# completed.net
KiCad netlist of a schematic drawn in Altium Designer
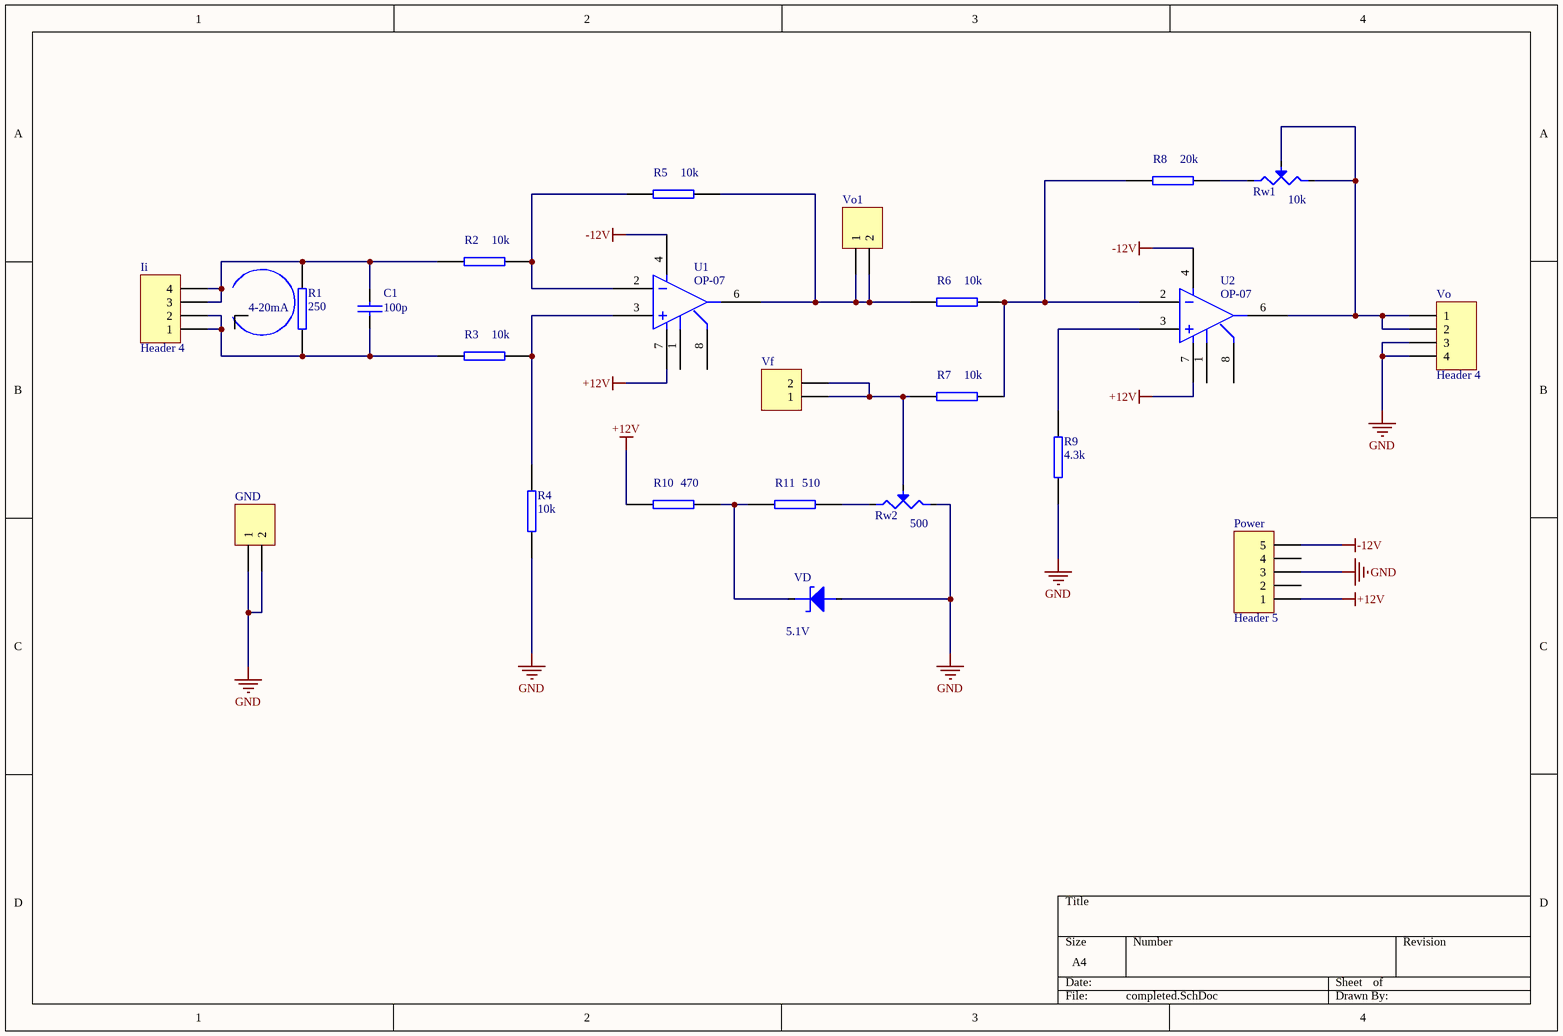
[diagram p0: completed.SchDoc]

(export (version "E")
  (design (tool "Eeschema 10.0.6"))
  (components
    (comp (ref "C1")
      (value "CAP")
      (footprint "RAD-0.2")
      (fields (field (name "ALTIUM_UNNAMED_1") "100p"))
      (libsource (lib "Schematic Linear") (part "CAP"))
    )
    (comp (ref "GND")
      (value "Header 2")
      (footprint "SIP-2")
      (description "Header, 2-Pin")
      (fields (field (name "PUBLISHER") "Altium Limited"))
      (libsource (lib "") (part "Header 2_1"))
    )
    (comp (ref "Ii")
      (value "Header 4")
      (footprint "SIP-4")
      (description "Header, 4-Pin")
      (fields (field (name "PUBLISHER") "Altium Limited"))
      (libsource (lib "Miscellaneous Connectors") (part "Header 4"))
    )
    (comp (ref "Power")
      (value "Header 5")
      (footprint "POWER PLUG5")
      (description "Header, 5-Pin")
      (fields (field (name "PUBLISHER") "Altium Limited"))
      (libsource (lib "Miscellaneous Connectors") (part "Header 5"))
    )
    (comp (ref "R1")
      (value "RES2")
      (footprint "AXIAL0.4")
      (fields (field (name "R1") "250"))
      (libsource (lib "Miscellaneous Devices") (part "RES2"))
    )
    (comp (ref "R2")
      (value "RES2")
      (footprint "AXIAL0.4")
      (fields (field (name "ALTIUM_UNNAMED_1") "10k"))
      (libsource (lib "Miscellaneous Devices") (part "RES2"))
    )
    (comp (ref "R3")
      (value "10k")
      (footprint "AXIAL0.4")
      (fields (field (name "Comment") "RES2"))
      (libsource (lib "Miscellaneous Devices") (part "RES2"))
    )
    (comp (ref "R4")
      (value "RES2")
      (footprint "AXIAL0.4")
      (fields (field (name "R1") "10k"))
      (libsource (lib "Miscellaneous Devices") (part "RES2"))
    )
    (comp (ref "R5")
      (value "RES2")
      (footprint "AXIAL0.4")
      (fields (field (name "ALTIUM_UNNAMED_1") "10k"))
      (libsource (lib "Miscellaneous Devices") (part "RES2"))
    )
    (comp (ref "R6")
      (value "10k")
      (footprint "AXIAL0.4")
      (fields (field (name "Comment") "RES2"))
      (libsource (lib "Miscellaneous Devices") (part "RES2"))
    )
    (comp (ref "R7")
      (value "RES2")
      (footprint "AXIAL0.4")
      (fields (field (name "ALTIUM_UNNAMED_1") "10k"))
      (libsource (lib "Miscellaneous Devices") (part "RES2"))
    )
    (comp (ref "R8")
      (value "20k")
      (footprint "AXIAL0.4")
      (fields (field (name "Comment") "RES2"))
      (libsource (lib "Miscellaneous Devices") (part "RES2"))
    )
    (comp (ref "R9")
      (value "4.3k")
      (footprint "AXIAL0.4")
      (fields (field (name "Comment") "RES2"))
      (libsource (lib "Miscellaneous Devices") (part "RES2"))
    )
    (comp (ref "R10")
      (value "RES2")
      (footprint "AXIAL0.4")
      (fields (field (name "VALUE'") "470"))
      (libsource (lib "Miscellaneous Devices") (part "RES2"))
    )
    (comp (ref "R11")
      (value "510")
      (footprint "AXIAL0.4")
      (fields (field (name "Comment") "RES2"))
      (libsource (lib "Miscellaneous Devices") (part "RES2"))
    )
    (comp (ref "Rw1")
      (value "10k")
      (footprint "VR-5")
      (description "Potentiometer")
      (fields (field (name "Comment") "POT1"))
      (libsource (lib "") (part "POT1_1"))
    )
    (comp (ref "Rw2")
      (value "500")
      (footprint "VR-5")
      (description "Potentiometer")
      (fields (field (name "Comment") "POT1"))
      (libsource (lib "Miscellaneous Devices") (part "POT1"))
    )
    (comp (ref "U1")
      (value "OP-07")
      (footprint "DIP-8")
      (libsource (lib "Schematic Operational Amplifiers") (part "OP-07"))
    )
    (comp (ref "U2")
      (value "OP-07")
      (footprint "DIP-8")
      (libsource (lib "Schematic Operational Amplifiers") (part "OP-07"))
    )
    (comp (ref "VD")
      (value "5.1V")
      (footprint "DIODE-0.4")
      (description "Zener Diode")
      (fields (field (name "Comment") "ZENER2"))
      (libsource (lib "Miscellaneous Devices") (part "ZENER2"))
    )
    (comp (ref "Vf")
      (value "Header 2")
      (footprint "SIP-2")
      (description "Header, 2-Pin")
      (fields (field (name "PUBLISHER") "Altium Limited"))
      (libsource (lib "Miscellaneous Connectors") (part "Header 2"))
    )
    (comp (ref "Vo")
      (value "Header 4")
      (footprint "SIP-4")
      (description "Header, 4-Pin")
      (fields (field (name "PUBLISHER") "Altium Limited"))
      (libsource (lib "") (part "Header 4_1"))
    )
    (comp (ref "Vo1")
      (value "Header 2")
      (footprint "SIP-2")
      (description "Header, 2-Pin")
      (fields (field (name "PUBLISHER") "Altium Limited"))
      (libsource (lib "") (part "Header 2_1"))
    )
  )
  (nets
    (net (code "1") (name "+12V") (class "Default")
      (node (ref "Power") (pin "1") (pinfunction "1_1") (pintype "passive"))
      (node (ref "R10") (pin "1") (pinfunction "1_1") (pintype "passive"))
      (node (ref "U1") (pin "7") (pintype "passive"))
      (node (ref "U2") (pin "7") (pintype "passive"))
    )
    (net (code "2") (name "-12V") (class "Default")
      (node (ref "Power") (pin "5") (pinfunction "5_5") (pintype "passive"))
      (node (ref "U1") (pin "4") (pintype "passive"))
      (node (ref "U2") (pin "4") (pintype "passive"))
    )
    (net (code "3") (name "GND") (class "Default")
      (node (ref "GND") (pin "1") (pinfunction "1_1") (pintype "passive"))
      (node (ref "GND") (pin "2") (pinfunction "2_2") (pintype "passive"))
      (node (ref "Power") (pin "3") (pinfunction "3_3") (pintype "passive"))
      (node (ref "R4") (pin "1") (pinfunction "1_1") (pintype "passive"))
      (node (ref "R9") (pin "1") (pinfunction "1_1") (pintype "passive"))
      (node (ref "Rw2") (pin "1") (pinfunction "2_1") (pintype "passive"))
      (node (ref "VD") (pin "1") (pinfunction "A_1") (pintype "passive"))
      (node (ref "Vo") (pin "3") (pinfunction "3_3") (pintype "passive"))
      (node (ref "Vo") (pin "4") (pinfunction "4_4") (pintype "passive"))
    )
    (net (code "4") (name "Net-(C1-Pad1)") (class "Default")
      (node (ref "C1") (pin "1") (pintype "passive"))
      (node (ref "Ii") (pin "3") (pinfunction "3_3") (pintype "passive"))
      (node (ref "Ii") (pin "4") (pinfunction "4_4") (pintype "passive"))
      (node (ref "R1") (pin "2") (pinfunction "2_2") (pintype "passive"))
      (node (ref "R2") (pin "1") (pinfunction "1_1") (pintype "passive"))
    )
    (net (code "5") (name "Net-(C1-Pad2)") (class "Default")
      (node (ref "C1") (pin "2") (pintype "passive"))
      (node (ref "Ii") (pin "1") (pinfunction "1_1") (pintype "passive"))
      (node (ref "Ii") (pin "2") (pinfunction "2_2") (pintype "passive"))
      (node (ref "R1") (pin "1") (pinfunction "1_1") (pintype "passive"))
      (node (ref "R3") (pin "1") (pinfunction "1_1") (pintype "passive"))
    )
    (net (code "6") (name "Net-(R2-Pad2)") (class "Default")
      (node (ref "R2") (pin "2") (pinfunction "2_2") (pintype "passive"))
      (node (ref "R5") (pin "1") (pinfunction "1_1") (pintype "passive"))
      (node (ref "U1") (pin "2") (pintype "passive"))
    )
    (net (code "7") (name "Net-(R3-Pad2)") (class "Default")
      (node (ref "R3") (pin "2") (pinfunction "2_2") (pintype "passive"))
      (node (ref "R4") (pin "2") (pinfunction "2_2") (pintype "passive"))
      (node (ref "U1") (pin "3") (pintype "passive"))
    )
    (net (code "8") (name "Net-(R5-Pad2)") (class "Default")
      (node (ref "R5") (pin "2") (pinfunction "2_2") (pintype "passive"))
      (node (ref "R6") (pin "1") (pinfunction "1_1") (pintype "passive"))
      (node (ref "U1") (pin "6") (pintype "passive"))
      (node (ref "Vo1") (pin "1") (pinfunction "1_1") (pintype "passive"))
      (node (ref "Vo1") (pin "2") (pinfunction "2_2") (pintype "passive"))
    )
    (net (code "9") (name "Net-(R6-Pad2)") (class "Default")
      (node (ref "R6") (pin "2") (pinfunction "2_2") (pintype "passive"))
      (node (ref "R7") (pin "2") (pinfunction "2_2") (pintype "passive"))
      (node (ref "R8") (pin "1") (pinfunction "1_1") (pintype "passive"))
      (node (ref "U2") (pin "2") (pintype "passive"))
    )
    (net (code "10") (name "Net-(R8-Pad2)") (class "Default")
      (node (ref "R8") (pin "2") (pinfunction "2_2") (pintype "passive"))
      (node (ref "Rw1") (pin "1") (pinfunction "1_1") (pintype "passive"))
    )
    (net (code "11") (name "Net-(R9-Pad2)") (class "Default")
      (node (ref "R9") (pin "2") (pinfunction "2_2") (pintype "passive"))
      (node (ref "U2") (pin "3") (pintype "passive"))
    )
    (net (code "12") (name "Net-(Rw1-W)") (class "Default")
      (node (ref "Rw1") (pin "2") (pinfunction "2_2") (pintype "passive"))
      (node (ref "Rw1") (pin "3") (pinfunction "W_3") (pintype "passive"))
      (node (ref "U2") (pin "6") (pintype "passive"))
      (node (ref "Vo") (pin "1") (pinfunction "1_1") (pintype "passive"))
      (node (ref "Vo") (pin "2") (pinfunction "2_2") (pintype "passive"))
    )
    (net (code "13") (name "Net-(Rw2-1)") (class "Default")
      (node (ref "R11") (pin "2") (pinfunction "2_2") (pintype "passive"))
      (node (ref "Rw2") (pin "2") (pinfunction "1_2") (pintype "passive"))
    )
    (net (code "14") (name "Net-(Rw2-W)") (class "Default")
      (node (ref "R7") (pin "1") (pinfunction "1_1") (pintype "passive"))
      (node (ref "Rw2") (pin "3") (pinfunction "W_3") (pintype "passive"))
      (node (ref "Vf") (pin "1") (pinfunction "1_1") (pintype "passive"))
      (node (ref "Vf") (pin "2") (pinfunction "2_2") (pintype "passive"))
    )
    (net (code "15") (name "Net-(VD-K)") (class "Default")
      (node (ref "R10") (pin "2") (pinfunction "2_2") (pintype "passive"))
      (node (ref "R11") (pin "1") (pinfunction "1_1") (pintype "passive"))
      (node (ref "VD") (pin "2") (pinfunction "K_2") (pintype "passive"))
    )
    (net (code "16") (name "unconnected-(Power-Pad2)") (class "Default")
      (node (ref "Power") (pin "2") (pinfunction "2_2") (pintype "passive"))
    )
    (net (code "17") (name "unconnected-(Power-Pad4)") (class "Default")
      (node (ref "Power") (pin "4") (pinfunction "4_4") (pintype "passive"))
    )
    (net (code "18") (name "unconnected-(U1-Pad1)") (class "Default")
      (node (ref "U1") (pin "1") (pintype "passive"))
    )
    (net (code "19") (name "unconnected-(U1-Pad8)") (class "Default")
      (node (ref "U1") (pin "8") (pintype "passive"))
    )
    (net (code "20") (name "unconnected-(U2-Pad1)") (class "Default")
      (node (ref "U2") (pin "1") (pintype "passive"))
    )
    (net (code "21") (name "unconnected-(U2-Pad8)") (class "Default")
      (node (ref "U2") (pin "8") (pintype "passive"))
    )
  )
)
